# shield.net
KiCad netlist of a schematic drawn in EAGLE
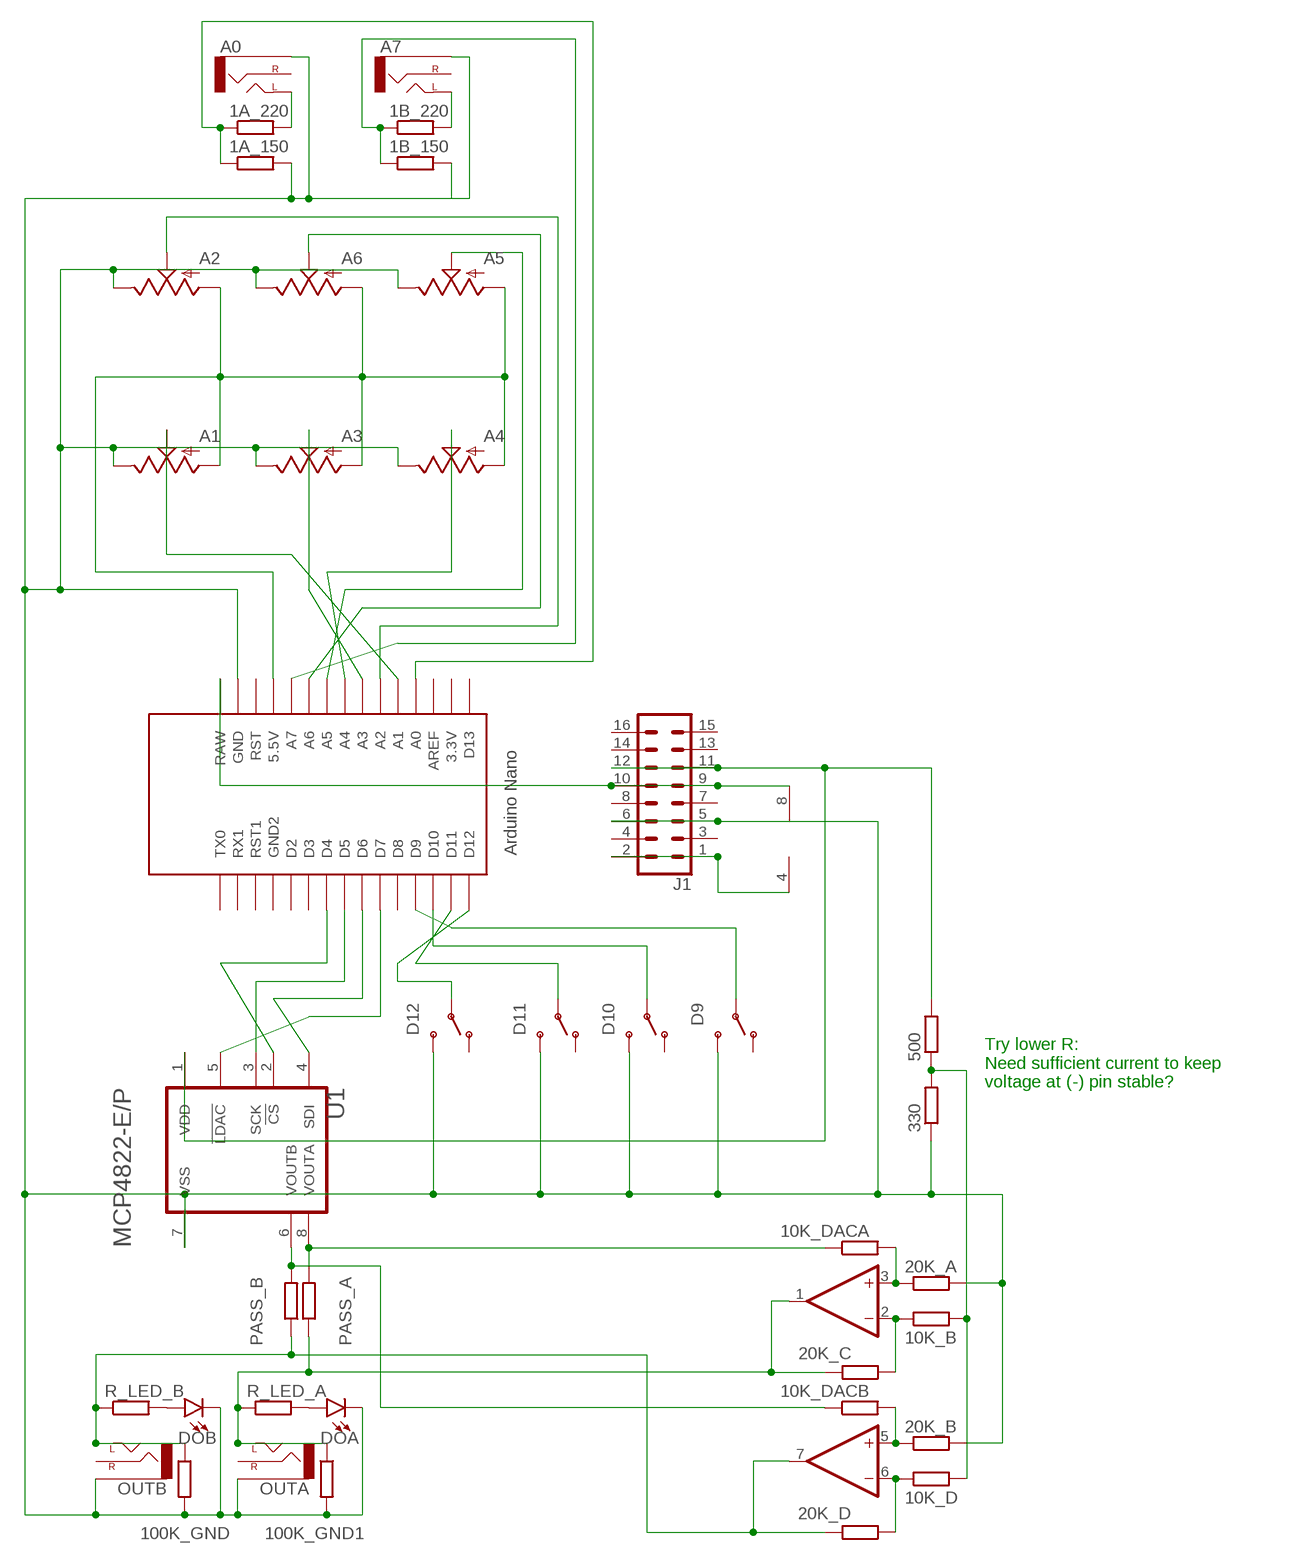
[diagram p0: schematic, sheet 1]

(export (version "E")
  (design (tool "Eeschema 10.0.6"))
  (components
    (comp (ref "1A_150")
      (value "RESISTOR7MM")
      (footprint "eagle-import:7MM_RESISTOR")
      (libsource (lib "eagle-import") (part "RESISTOR7MM"))
    )
    (comp (ref "1A_220")
      (value "RESISTOR7MM")
      (footprint "eagle-import:7MM_RESISTOR")
      (libsource (lib "eagle-import") (part "RESISTOR7MM"))
    )
    (comp (ref "1B_150")
      (value "RESISTOR7MM")
      (footprint "eagle-import:7MM_RESISTOR")
      (libsource (lib "eagle-import") (part "RESISTOR7MM"))
    )
    (comp (ref "1B_220")
      (value "RESISTOR7MM")
      (footprint "eagle-import:7MM_RESISTOR")
      (libsource (lib "eagle-import") (part "RESISTOR7MM"))
    )
    (comp (ref "10K_B")
      (value "RESISTOR7MM")
      (footprint "eagle-import:7MM_RESISTOR")
      (libsource (lib "eagle-import") (part "RESISTOR7MM"))
    )
    (comp (ref "10K_D")
      (value "RESISTOR7MM")
      (footprint "eagle-import:7MM_RESISTOR")
      (libsource (lib "eagle-import") (part "RESISTOR7MM"))
    )
    (comp (ref "10K_DACA")
      (value "RESISTOR7MM")
      (footprint "eagle-import:7MM_RESISTOR")
      (libsource (lib "eagle-import") (part "RESISTOR7MM"))
    )
    (comp (ref "10K_DACB")
      (value "RESISTOR7MM")
      (footprint "eagle-import:7MM_RESISTOR")
      (libsource (lib "eagle-import") (part "RESISTOR7MM"))
    )
    (comp (ref "20K_A")
      (value "RESISTOR7MM")
      (footprint "eagle-import:7MM_RESISTOR")
      (libsource (lib "eagle-import") (part "RESISTOR7MM"))
    )
    (comp (ref "20K_B")
      (value "RESISTOR7MM")
      (footprint "eagle-import:7MM_RESISTOR")
      (libsource (lib "eagle-import") (part "RESISTOR7MM"))
    )
    (comp (ref "20K_C")
      (value "RESISTOR7MM")
      (footprint "eagle-import:7MM_RESISTOR")
      (libsource (lib "eagle-import") (part "RESISTOR7MM"))
    )
    (comp (ref "20K_D")
      (value "RESISTOR7MM")
      (footprint "eagle-import:7MM_RESISTOR")
      (libsource (lib "eagle-import") (part "RESISTOR7MM"))
    )
    (comp (ref "100K_GND")
      (value "RESISTOR7MM")
      (footprint "eagle-import:7MM_RESISTOR")
      (libsource (lib "eagle-import") (part "RESISTOR7MM"))
    )
    (comp (ref "100K_GND1")
      (value "RESISTOR7MM")
      (footprint "eagle-import:7MM_RESISTOR")
      (libsource (lib "eagle-import") (part "RESISTOR7MM"))
    )
    (comp (ref "330")
      (value "RESISTOR7MM")
      (footprint "eagle-import:7MM_RESISTOR")
      (libsource (lib "eagle-import") (part "RESISTOR7MM"))
    )
    (comp (ref "500")
      (value "RESISTOR7MM")
      (footprint "eagle-import:7MM_RESISTOR")
      (libsource (lib "eagle-import") (part "RESISTOR7MM"))
    )
    (comp (ref "A0")
      (value "THONKI-STEREO")
      (footprint "eagle-import:WQP-PJ366ST_JACK")
      (libsource (lib "eagle-import") (part "THONKI-STEREO"))
    )
    (comp (ref "A1")
      (value "9MM_SNAP-IN_POT_")
      (footprint "eagle-import:9MM_SNAP-IN_POT")
      (libsource (lib "eagle-import") (part "9MM_SNAP-IN_POT_"))
    )
    (comp (ref "A2")
      (value "9MM_SNAP-IN_POT_")
      (footprint "eagle-import:9MM_SNAP-IN_POT")
      (libsource (lib "eagle-import") (part "9MM_SNAP-IN_POT_"))
    )
    (comp (ref "A3")
      (value "9MM_SNAP-IN_POT_")
      (footprint "eagle-import:9MM_SNAP-IN_POT")
      (libsource (lib "eagle-import") (part "9MM_SNAP-IN_POT_"))
    )
    (comp (ref "A4")
      (value "9MM_SNAP-IN_POT_")
      (footprint "eagle-import:9MM_SNAP-IN_POT")
      (libsource (lib "eagle-import") (part "9MM_SNAP-IN_POT_"))
    )
    (comp (ref "A5")
      (value "9MM_SNAP-IN_POT_")
      (footprint "eagle-import:9MM_SNAP-IN_POT")
      (libsource (lib "eagle-import") (part "9MM_SNAP-IN_POT_"))
    )
    (comp (ref "A6")
      (value "9MM_SNAP-IN_POT_")
      (footprint "eagle-import:9MM_SNAP-IN_POT")
      (libsource (lib "eagle-import") (part "9MM_SNAP-IN_POT_"))
    )
    (comp (ref "A7")
      (value "THONKI-STEREO")
      (footprint "eagle-import:WQP-PJ366ST_JACK")
      (libsource (lib "eagle-import") (part "THONKI-STEREO"))
    )
    (comp (ref "D9")
      (value "SUBMINI_SPDT")
      (footprint "eagle-import:SUBMINI_TOGGLE")
      (libsource (lib "eagle-import") (part "SUBMINI_SPDT"))
    )
    (comp (ref "D10")
      (value "SUBMINI_SPDT")
      (footprint "eagle-import:SUBMINI_TOGGLE")
      (libsource (lib "eagle-import") (part "SUBMINI_SPDT"))
    )
    (comp (ref "D11")
      (value "SUBMINI_SPDT")
      (footprint "eagle-import:SUBMINI_TOGGLE")
      (libsource (lib "eagle-import") (part "SUBMINI_SPDT"))
    )
    (comp (ref "D12")
      (value "SUBMINI_SPDT")
      (footprint "eagle-import:SUBMINI_TOGGLE")
      (libsource (lib "eagle-import") (part "SUBMINI_SPDT"))
    )
    (comp (ref "DOA")
      (value "LED3MM")
      (footprint "eagle-import:LED_3MM")
      (libsource (lib "eagle-import") (part "LED3MM"))
    )
    (comp (ref "DOB")
      (value "LED3MM")
      (footprint "eagle-import:LED_3MM")
      (libsource (lib "eagle-import") (part "LED3MM"))
    )
    (comp (ref "IC1")
      (value "TL072P")
      (footprint "eagle-import:DIL08")
      (libsource (lib "eagle-import") (part "TL072P"))
    )
    (comp (ref "J1")
      (value "CONN_08X2")
      (footprint "eagle-import:2X8")
      (libsource (lib "eagle-import") (part "CONN_08X2"))
    )
    (comp (ref "OUTA")
      (value "THONKI-STEREO")
      (footprint "eagle-import:WQP-PJ366ST_JACK")
      (libsource (lib "eagle-import") (part "THONKI-STEREO"))
    )
    (comp (ref "OUTB")
      (value "THONKI-STEREO")
      (footprint "eagle-import:WQP-PJ366ST_JACK")
      (libsource (lib "eagle-import") (part "THONKI-STEREO"))
    )
    (comp (ref "PASS_A")
      (value "RESISTOR7MM")
      (footprint "eagle-import:7MM_RESISTOR")
      (libsource (lib "eagle-import") (part "RESISTOR7MM"))
    )
    (comp (ref "PASS_B")
      (value "RESISTOR7MM")
      (footprint "eagle-import:7MM_RESISTOR")
      (libsource (lib "eagle-import") (part "RESISTOR7MM"))
    )
    (comp (ref "R_LED_A")
      (value "RESISTOR7MM")
      (footprint "eagle-import:7MM_RESISTOR")
      (libsource (lib "eagle-import") (part "RESISTOR7MM"))
    )
    (comp (ref "R_LED_B")
      (value "RESISTOR7MM")
      (footprint "eagle-import:7MM_RESISTOR")
      (libsource (lib "eagle-import") (part "RESISTOR7MM"))
    )
    (comp (ref "U$1")
      (value "NANO")
      (footprint "eagle-import:NANO")
      (libsource (lib "eagle-import") (part "NANO"))
    )
    (comp (ref "U1")
      (value "MICROCHIP_MCP4822-E-PMICROCHIP_MCP4822-E-P_0_0")
      (footprint "eagle-import:MICROCHIP_MCP4822-E-P_0")
      (fields (field (name "MF") "Microchip") (field (name "MPN") "MCP4822-E/P"))
      (libsource (lib "eagle-import") (part "MICROCHIP_MCP4822-E-PMICROCHIP_MCP4822-E-P_0_0"))
    )
  )
  (nets
    (net (code "1") (name "Net-(1A_150-Pad1)") (class "Default")
      (node (ref "1A_150") (pin "1") (pinfunction "1_1") (pintype "passive"))
      (node (ref "1A_220") (pin "1") (pinfunction "1_1") (pintype "passive"))
      (node (ref "U$1") (pin "A0") (pinfunction "A0_A0") (pintype "bidirectional"))
    )
    (net (code "2") (name "Net-(1B_150-Pad1)") (class "Default")
      (node (ref "1B_150") (pin "1") (pinfunction "1_1") (pintype "passive"))
      (node (ref "1B_220") (pin "1") (pinfunction "1_1") (pintype "passive"))
      (node (ref "U$1") (pin "A7") (pinfunction "A7_A7") (pintype "bidirectional"))
    )
    (net (code "3") (name "Net-(10K_B-Pad2)") (class "Default")
      (node (ref "10K_B") (pin "2") (pinfunction "2_2") (pintype "passive"))
      (node (ref "10K_D") (pin "2") (pinfunction "2_2") (pintype "passive"))
      (node (ref "330") (pin "2") (pinfunction "2_2") (pintype "passive"))
      (node (ref "500") (pin "1") (pinfunction "1_1") (pintype "passive"))
    )
    (net (code "4") (name "Net-(A0-LEFT)") (class "Default")
      (node (ref "1A_220") (pin "2") (pinfunction "2_2") (pintype "passive"))
      (node (ref "A0") (pin "P$1_TIP") (pinfunction "LEFT_P$1_TIP") (pintype "bidirectional"))
    )
    (net (code "5") (name "Net-(A0-SLEEVE)") (class "Default")
      (node (ref "100K_GND") (pin "2") (pinfunction "2_2") (pintype "passive"))
      (node (ref "100K_GND1") (pin "2") (pinfunction "2_2") (pintype "passive"))
      (node (ref "1A_150") (pin "2") (pinfunction "2_2") (pintype "passive"))
      (node (ref "1B_150") (pin "2") (pinfunction "2_2") (pintype "passive"))
      (node (ref "20K_A") (pin "2") (pinfunction "2_2") (pintype "passive"))
      (node (ref "20K_B") (pin "2") (pinfunction "2_2") (pintype "passive"))
      (node (ref "330") (pin "1") (pinfunction "1_1") (pintype "passive"))
      (node (ref "A0") (pin "P$3_SLEEVE") (pinfunction "SLEEVE_P$3_SLEEVE") (pintype "bidirectional"))
      (node (ref "A1") (pin "3") (pinfunction "E_3") (pintype "passive"))
      (node (ref "A2") (pin "3") (pinfunction "E_3") (pintype "passive"))
      (node (ref "A3") (pin "3") (pinfunction "E_3") (pintype "passive"))
      (node (ref "A4") (pin "3") (pinfunction "E_3") (pintype "passive"))
      (node (ref "A5") (pin "3") (pinfunction "E_3") (pintype "passive"))
      (node (ref "A6") (pin "3") (pinfunction "E_3") (pintype "passive"))
      (node (ref "A7") (pin "P$3_SLEEVE") (pinfunction "SLEEVE_P$3_SLEEVE") (pintype "bidirectional"))
      (node (ref "D10") (pin "3") (pinfunction "S_3") (pintype "passive"))
      (node (ref "D11") (pin "3") (pinfunction "S_3") (pintype "passive"))
      (node (ref "D12") (pin "3") (pinfunction "S_3") (pintype "passive"))
      (node (ref "D9") (pin "3") (pinfunction "S_3") (pintype "passive"))
      (node (ref "DOA") (pin "K") (pinfunction "C_K") (pintype "passive"))
      (node (ref "DOB") (pin "K") (pinfunction "C_K") (pintype "passive"))
      (node (ref "J1") (pin "5") (pinfunction "5_5") (pintype "passive"))
      (node (ref "J1") (pin "6") (pinfunction "6_6") (pintype "passive"))
      (node (ref "OUTA") (pin "P$3_SLEEVE") (pinfunction "SLEEVE_P$3_SLEEVE") (pintype "bidirectional"))
      (node (ref "OUTB") (pin "P$3_SLEEVE") (pinfunction "SLEEVE_P$3_SLEEVE") (pintype "bidirectional"))
      (node (ref "U$1") (pin "GND") (pinfunction "GND_GND") (pintype "bidirectional"))
      (node (ref "U1") (pin "7") (pinfunction "VSS_7") (pintype "power_in"))
    )
    (net (code "6") (name "Net-(A1-A)") (class "Default")
      (node (ref "A1") (pin "1") (pinfunction "A_1") (pintype "passive"))
      (node (ref "A2") (pin "1") (pinfunction "A_1") (pintype "passive"))
      (node (ref "A3") (pin "1") (pinfunction "A_1") (pintype "passive"))
      (node (ref "A4") (pin "1") (pinfunction "A_1") (pintype "passive"))
      (node (ref "A5") (pin "1") (pinfunction "A_1") (pintype "passive"))
      (node (ref "A6") (pin "1") (pinfunction "A_1") (pintype "passive"))
      (node (ref "U$1") (pin "5V") (pinfunction "5.5V_5V") (pintype "bidirectional"))
    )
    (net (code "7") (name "Net-(A1-S)") (class "Default")
      (node (ref "A1") (pin "2") (pinfunction "S_2") (pintype "passive"))
      (node (ref "U$1") (pin "A1") (pinfunction "A1_A1") (pintype "bidirectional"))
    )
    (net (code "8") (name "Net-(A2-S)") (class "Default")
      (node (ref "A2") (pin "2") (pinfunction "S_2") (pintype "passive"))
      (node (ref "U$1") (pin "A2") (pinfunction "A2_A2") (pintype "bidirectional"))
    )
    (net (code "9") (name "Net-(A3-S)") (class "Default")
      (node (ref "A3") (pin "2") (pinfunction "S_2") (pintype "passive"))
      (node (ref "U$1") (pin "A3") (pinfunction "A3_A3") (pintype "bidirectional"))
    )
    (net (code "10") (name "Net-(A4-S)") (class "Default")
      (node (ref "A4") (pin "2") (pinfunction "S_2") (pintype "passive"))
      (node (ref "U$1") (pin "A4") (pinfunction "A4_A4") (pintype "bidirectional"))
    )
    (net (code "11") (name "Net-(A5-S)") (class "Default")
      (node (ref "A5") (pin "2") (pinfunction "S_2") (pintype "passive"))
      (node (ref "U$1") (pin "A5") (pinfunction "A5_A5") (pintype "bidirectional"))
    )
    (net (code "12") (name "Net-(A6-S)") (class "Default")
      (node (ref "A6") (pin "2") (pinfunction "S_2") (pintype "passive"))
      (node (ref "U$1") (pin "A6") (pinfunction "A6_A6") (pintype "bidirectional"))
    )
    (net (code "13") (name "Net-(A7-LEFT)") (class "Default")
      (node (ref "1B_220") (pin "2") (pinfunction "2_2") (pintype "passive"))
      (node (ref "A7") (pin "P$1_TIP") (pinfunction "LEFT_P$1_TIP") (pintype "bidirectional"))
    )
    (net (code "14") (name "Net-(D9-COMMON)") (class "Default")
      (node (ref "D9") (pin "COM") (pinfunction "COMMON_COM") (pintype "passive"))
      (node (ref "U$1") (pin "D9") (pinfunction "D9_D9") (pintype "bidirectional"))
    )
    (net (code "15") (name "Net-(D10-COMMON)") (class "Default")
      (node (ref "D10") (pin "COM") (pinfunction "COMMON_COM") (pintype "passive"))
      (node (ref "U$1") (pin "D10") (pinfunction "D10_D10") (pintype "bidirectional"))
    )
    (net (code "16") (name "Net-(D11-COMMON)") (class "Default")
      (node (ref "D11") (pin "COM") (pinfunction "COMMON_COM") (pintype "passive"))
      (node (ref "U$1") (pin "D11") (pinfunction "D11_D11") (pintype "bidirectional"))
    )
    (net (code "17") (name "Net-(D12-COMMON)") (class "Default")
      (node (ref "D12") (pin "COM") (pinfunction "COMMON_COM") (pintype "passive"))
      (node (ref "U$1") (pin "D12") (pinfunction "D12_D12") (pintype "bidirectional"))
    )
    (net (code "18") (name "Net-(DOA-PadA)") (class "Default")
      (node (ref "DOA") (pin "A") (pinfunction "A_A") (pintype "passive"))
      (node (ref "R_LED_A") (pin "2") (pinfunction "2_2") (pintype "passive"))
    )
    (net (code "19") (name "Net-(DOB-PadA)") (class "Default")
      (node (ref "DOB") (pin "A") (pinfunction "A_A") (pintype "passive"))
      (node (ref "R_LED_B") (pin "2") (pinfunction "2_2") (pintype "passive"))
    )
    (net (code "20") (name "Net-(IC1A-+IN)") (class "Default")
      (node (ref "10K_DACA") (pin "2") (pinfunction "2_2") (pintype "passive"))
      (node (ref "20K_A") (pin "1") (pinfunction "1_1") (pintype "passive"))
      (node (ref "IC1") (pin "3") (pinfunction "+IN_3") (pintype "input"))
    )
    (net (code "21") (name "Net-(IC1A--IN)") (class "Default")
      (node (ref "10K_B") (pin "1") (pinfunction "1_1") (pintype "passive"))
      (node (ref "20K_C") (pin "1") (pinfunction "1_1") (pintype "passive"))
      (node (ref "IC1") (pin "2") (pinfunction "-IN_2") (pintype "input"))
    )
    (net (code "22") (name "Net-(IC1A-OUT)") (class "Default")
      (node (ref "100K_GND1") (pin "1") (pinfunction "1_1") (pintype "passive"))
      (node (ref "20K_C") (pin "2") (pinfunction "2_2") (pintype "passive"))
      (node (ref "IC1") (pin "1") (pinfunction "OUT_1") (pintype "output"))
      (node (ref "OUTA") (pin "P$1_TIP") (pinfunction "LEFT_P$1_TIP") (pintype "bidirectional"))
      (node (ref "PASS_A") (pin "1") (pinfunction "1_1") (pintype "passive"))
      (node (ref "R_LED_A") (pin "1") (pinfunction "1_1") (pintype "passive"))
    )
    (net (code "23") (name "Net-(IC1B-+IN)") (class "Default")
      (node (ref "10K_DACB") (pin "2") (pinfunction "2_2") (pintype "passive"))
      (node (ref "20K_B") (pin "1") (pinfunction "1_1") (pintype "passive"))
      (node (ref "IC1") (pin "5") (pinfunction "+IN_5") (pintype "input"))
    )
    (net (code "24") (name "Net-(IC1B--IN)") (class "Default")
      (node (ref "10K_D") (pin "1") (pinfunction "1_1") (pintype "passive"))
      (node (ref "20K_D") (pin "1") (pinfunction "1_1") (pintype "passive"))
      (node (ref "IC1") (pin "6") (pinfunction "-IN_6") (pintype "input"))
    )
    (net (code "25") (name "Net-(IC1B-OUT)") (class "Default")
      (node (ref "100K_GND") (pin "1") (pinfunction "1_1") (pintype "passive"))
      (node (ref "20K_D") (pin "2") (pinfunction "2_2") (pintype "passive"))
      (node (ref "IC1") (pin "7") (pinfunction "OUT_7") (pintype "output"))
      (node (ref "OUTB") (pin "P$1_TIP") (pinfunction "LEFT_P$1_TIP") (pintype "bidirectional"))
      (node (ref "PASS_B") (pin "1") (pinfunction "1_1") (pintype "passive"))
      (node (ref "R_LED_B") (pin "1") (pinfunction "1_1") (pintype "passive"))
    )
    (net (code "26") (name "Net-(IC1C-V+)") (class "Default")
      (node (ref "IC1") (pin "8") (pinfunction "V+_8") (pintype "power_in"))
      (node (ref "J1") (pin "10") (pinfunction "10_10") (pintype "passive"))
      (node (ref "J1") (pin "9") (pinfunction "9_9") (pintype "passive"))
      (node (ref "U$1") (pin "RAW") (pinfunction "RAW_RAW") (pintype "bidirectional"))
    )
    (net (code "27") (name "Net-(IC1C-V-)") (class "Default")
      (node (ref "IC1") (pin "4") (pinfunction "V-_4") (pintype "power_in"))
      (node (ref "J1") (pin "1") (pinfunction "1_1") (pintype "passive"))
      (node (ref "J1") (pin "2") (pinfunction "2_2") (pintype "passive"))
    )
    (net (code "28") (name "Net-(U1-SCK)") (class "Default")
      (node (ref "U$1") (pin "D5") (pinfunction "D5_D5") (pintype "bidirectional"))
      (node (ref "U1") (pin "3") (pinfunction "SCK_3") (pintype "input"))
    )
    (net (code "29") (name "Net-(U1-SDI)") (class "Default")
      (node (ref "U$1") (pin "D6") (pinfunction "D6_D6") (pintype "bidirectional"))
      (node (ref "U1") (pin "4") (pinfunction "SDI_4") (pintype "input"))
    )
    (net (code "30") (name "Net-(U1-VDD)") (class "Default")
      (node (ref "500") (pin "2") (pinfunction "2_2") (pintype "passive"))
      (node (ref "J1") (pin "11") (pinfunction "11_11") (pintype "passive"))
      (node (ref "J1") (pin "12") (pinfunction "12_12") (pintype "passive"))
      (node (ref "U1") (pin "1") (pinfunction "VDD_1") (pintype "power_in"))
    )
    (net (code "31") (name "Net-(U1-VOUTA)") (class "Default")
      (node (ref "10K_DACA") (pin "1") (pinfunction "1_1") (pintype "passive"))
      (node (ref "PASS_A") (pin "2") (pinfunction "2_2") (pintype "passive"))
      (node (ref "U1") (pin "8") (pinfunction "VOUTA_8") (pintype "output"))
    )
    (net (code "32") (name "Net-(U1-VOUTB)") (class "Default")
      (node (ref "10K_DACB") (pin "1") (pinfunction "1_1") (pintype "passive"))
      (node (ref "PASS_B") (pin "2") (pinfunction "2_2") (pintype "passive"))
      (node (ref "U1") (pin "6") (pinfunction "VOUTB_6") (pintype "output"))
    )
    (net (code "33") (name "Net-(U1-~{CS})") (class "Default")
      (node (ref "U$1") (pin "D4") (pinfunction "D4_D4") (pintype "bidirectional"))
      (node (ref "U1") (pin "2") (pinfunction "~{CS}_2") (pintype "input"))
    )
    (net (code "34") (name "Net-(U1-~{LDAC})") (class "Default")
      (node (ref "U$1") (pin "D7") (pinfunction "D7_D7") (pintype "bidirectional"))
      (node (ref "U1") (pin "5") (pinfunction "~{LDAC}_5") (pintype "input"))
    )
    (net (code "35") (name "unconnected-(A0-RIGHT-PadP$2_SWITCH)") (class "Default")
      (node (ref "A0") (pin "P$2_SWITCH") (pinfunction "RIGHT_P$2_SWITCH") (pintype "bidirectional"))
    )
    (net (code "36") (name "unconnected-(A7-RIGHT-PadP$2_SWITCH)") (class "Default")
      (node (ref "A7") (pin "P$2_SWITCH") (pinfunction "RIGHT_P$2_SWITCH") (pintype "bidirectional"))
    )
    (net (code "37") (name "unconnected-(D9-O-Pad1)") (class "Default")
      (node (ref "D9") (pin "1") (pinfunction "O_1") (pintype "passive"))
    )
    (net (code "38") (name "unconnected-(D10-O-Pad1)") (class "Default")
      (node (ref "D10") (pin "1") (pinfunction "O_1") (pintype "passive"))
    )
    (net (code "39") (name "unconnected-(D11-O-Pad1)") (class "Default")
      (node (ref "D11") (pin "1") (pinfunction "O_1") (pintype "passive"))
    )
    (net (code "40") (name "unconnected-(D12-O-Pad1)") (class "Default")
      (node (ref "D12") (pin "1") (pinfunction "O_1") (pintype "passive"))
    )
    (net (code "41") (name "unconnected-(J1-Pad3)") (class "Default")
      (node (ref "J1") (pin "3") (pinfunction "3_3") (pintype "passive"))
    )
    (net (code "42") (name "unconnected-(J1-Pad4)") (class "Default")
      (node (ref "J1") (pin "4") (pinfunction "4_4") (pintype "passive"))
    )
    (net (code "43") (name "unconnected-(J1-Pad7)") (class "Default")
      (node (ref "J1") (pin "7") (pinfunction "7_7") (pintype "passive"))
    )
    (net (code "44") (name "unconnected-(J1-Pad8)") (class "Default")
      (node (ref "J1") (pin "8") (pinfunction "8_8") (pintype "passive"))
    )
    (net (code "45") (name "unconnected-(J1-Pad13)") (class "Default")
      (node (ref "J1") (pin "13") (pinfunction "13_13") (pintype "passive"))
    )
    (net (code "46") (name "unconnected-(J1-Pad14)") (class "Default")
      (node (ref "J1") (pin "14") (pinfunction "14_14") (pintype "passive"))
    )
    (net (code "47") (name "unconnected-(J1-Pad15)") (class "Default")
      (node (ref "J1") (pin "15") (pinfunction "15_15") (pintype "passive"))
    )
    (net (code "48") (name "unconnected-(J1-Pad16)") (class "Default")
      (node (ref "J1") (pin "16") (pinfunction "16_16") (pintype "passive"))
    )
    (net (code "49") (name "unconnected-(OUTA-RIGHT-PadP$2_SWITCH)") (class "Default")
      (node (ref "OUTA") (pin "P$2_SWITCH") (pinfunction "RIGHT_P$2_SWITCH") (pintype "bidirectional"))
    )
    (net (code "50") (name "unconnected-(OUTB-RIGHT-PadP$2_SWITCH)") (class "Default")
      (node (ref "OUTB") (pin "P$2_SWITCH") (pinfunction "RIGHT_P$2_SWITCH") (pintype "bidirectional"))
    )
    (net (code "51") (name "unconnected-(U$1-GND2-PadGND1)") (class "Default")
      (node (ref "U$1") (pin "GND1") (pinfunction "GND2_GND1") (pintype "bidirectional"))
    )
    (net (code "52") (name "unconnected-(U$1-Pad3.3V)") (class "Default")
      (node (ref "U$1") (pin "3.3V") (pinfunction "3.3V_3.3V") (pintype "bidirectional"))
    )
    (net (code "53") (name "unconnected-(U$1-PadAREF)") (class "Default")
      (node (ref "U$1") (pin "AREF") (pinfunction "AREF_AREF") (pintype "bidirectional"))
    )
    (net (code "54") (name "unconnected-(U$1-PadD2)") (class "Default")
      (node (ref "U$1") (pin "D2") (pinfunction "D2_D2") (pintype "bidirectional"))
    )
    (net (code "55") (name "unconnected-(U$1-PadD3)") (class "Default")
      (node (ref "U$1") (pin "D3") (pinfunction "D3_D3") (pintype "bidirectional"))
    )
    (net (code "56") (name "unconnected-(U$1-PadD8)") (class "Default")
      (node (ref "U$1") (pin "D8") (pinfunction "D8_D8") (pintype "bidirectional"))
    )
    (net (code "57") (name "unconnected-(U$1-PadD13)") (class "Default")
      (node (ref "U$1") (pin "D13") (pinfunction "D13_D13") (pintype "bidirectional"))
    )
    (net (code "58") (name "unconnected-(U$1-PadICSP1)") (class "Default")
      (node (ref "U$1") (pin "ICSP1") (pinfunction "ICSP1_ICSP1") (pintype "bidirectional"))
    )
    (net (code "59") (name "unconnected-(U$1-PadICSP2)") (class "Default")
      (node (ref "U$1") (pin "ICSP2") (pinfunction "ICSP2_ICSP2") (pintype "bidirectional"))
    )
    (net (code "60") (name "unconnected-(U$1-PadICSP3)") (class "Default")
      (node (ref "U$1") (pin "ICSP3") (pinfunction "ICSP3_ICSP3") (pintype "bidirectional"))
    )
    (net (code "61") (name "unconnected-(U$1-PadICSP4)") (class "Default")
      (node (ref "U$1") (pin "ICSP4") (pinfunction "ICSP4_ICSP4") (pintype "bidirectional"))
    )
    (net (code "62") (name "unconnected-(U$1-PadICSP5)") (class "Default")
      (node (ref "U$1") (pin "ICSP5") (pinfunction "ICSP5_ICSP5") (pintype "bidirectional"))
    )
    (net (code "63") (name "unconnected-(U$1-PadICSP6)") (class "Default")
      (node (ref "U$1") (pin "ICSP6") (pinfunction "ICSP6_ICSP6") (pintype "bidirectional"))
    )
    (net (code "64") (name "unconnected-(U$1-PadRST)") (class "Default")
      (node (ref "U$1") (pin "RST") (pinfunction "RST_RST") (pintype "bidirectional"))
    )
    (net (code "65") (name "unconnected-(U$1-PadRST1)") (class "Default")
      (node (ref "U$1") (pin "RST1") (pinfunction "RST1_RST1") (pintype "bidirectional"))
    )
    (net (code "66") (name "unconnected-(U$1-PadRX1)") (class "Default")
      (node (ref "U$1") (pin "RX1") (pinfunction "RX1_RX1") (pintype "bidirectional"))
    )
    (net (code "67") (name "unconnected-(U$1-PadTX0)") (class "Default")
      (node (ref "U$1") (pin "TX0") (pinfunction "TX0_TX0") (pintype "bidirectional"))
    )
  )
)
